# Accelerometer_Test_Board.net
KiCad netlist of a schematic drawn in EAGLE
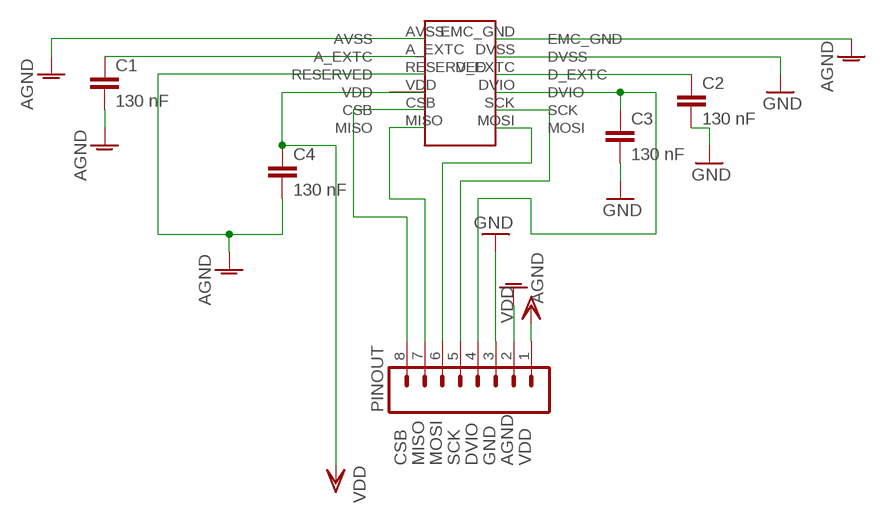
[diagram p0: schematic, sheet 1]

(export (version "E")
  (design (tool "Eeschema 10.0.6"))
  (components
    (comp (ref "C1")
      (value "130 nF")
      (footprint "eagle-import:0805")
      (libsource (lib "eagle-import") (part "CAP0805"))
    )
    (comp (ref "C2")
      (value "130 nF")
      (footprint "eagle-import:0805")
      (libsource (lib "eagle-import") (part "CAP0805"))
    )
    (comp (ref "C3")
      (value "130 nF")
      (footprint "eagle-import:0805")
      (libsource (lib "eagle-import") (part "CAP0805"))
    )
    (comp (ref "C4")
      (value "130 nF")
      (footprint "eagle-import:0805")
      (libsource (lib "eagle-import") (part "CAP0805"))
    )
    (comp (ref "PINOUT")
      (value "M08")
      (footprint "eagle-import:1X08")
      (libsource (lib "eagle-import") (part "M08"))
    )
    (comp (ref "U$1")
      (value "SCA3100-D04")
      (footprint "eagle-import:SCA3100-D04")
      (libsource (lib "eagle-import") (part "SCA3100-D04"))
    )
  )
  (nets
    (net (code "1") (name "/CSB") (class "Default")
      (node (ref "PINOUT") (pin "8") (pinfunction "8_8") (pintype "passive"))
      (node (ref "U$1") (pin "CSB") (pinfunction "CSB_CSB") (pintype "bidirectional"))
    )
    (net (code "2") (name "/DVIO") (class "Default")
      (node (ref "C3") (pin "1") (pinfunction "1_1") (pintype "passive"))
      (node (ref "PINOUT") (pin "4") (pinfunction "4_4") (pintype "passive"))
      (node (ref "U$1") (pin "DVIO") (pinfunction "DVIO_DVIO") (pintype "bidirectional"))
    )
    (net (code "3") (name "/MISO") (class "Default")
      (node (ref "PINOUT") (pin "7") (pinfunction "7_7") (pintype "passive"))
      (node (ref "U$1") (pin "MISO") (pinfunction "MISO_MISO") (pintype "bidirectional"))
    )
    (net (code "4") (name "/MOSI") (class "Default")
      (node (ref "PINOUT") (pin "6") (pinfunction "6_6") (pintype "passive"))
      (node (ref "U$1") (pin "MOSI") (pinfunction "MOSI_MOSI") (pintype "bidirectional"))
    )
    (net (code "5") (name "/SCK") (class "Default")
      (node (ref "PINOUT") (pin "5") (pinfunction "5_5") (pintype "passive"))
      (node (ref "U$1") (pin "SCK") (pinfunction "SCK_SCK") (pintype "bidirectional"))
    )
    (net (code "6") (name "AGND") (class "Default")
      (node (ref "C1") (pin "2") (pinfunction "2_2") (pintype "passive"))
      (node (ref "C4") (pin "2") (pinfunction "2_2") (pintype "passive"))
      (node (ref "PINOUT") (pin "2") (pinfunction "2_2") (pintype "passive"))
      (node (ref "U$1") (pin "AVSS") (pinfunction "AVSS_AVSS") (pintype "bidirectional"))
      (node (ref "U$1") (pin "EMC_GND") (pinfunction "EMC_GND_EMC_GND") (pintype "bidirectional"))
      (node (ref "U$1") (pin "RESERVED") (pinfunction "RESERVED_RESERVED") (pintype "bidirectional"))
    )
    (net (code "7") (name "GND") (class "Default")
      (node (ref "C2") (pin "2") (pinfunction "2_2") (pintype "passive"))
      (node (ref "C3") (pin "2") (pinfunction "2_2") (pintype "passive"))
      (node (ref "PINOUT") (pin "3") (pinfunction "3_3") (pintype "passive"))
      (node (ref "U$1") (pin "DVSS") (pinfunction "DVSS_DVSS") (pintype "bidirectional"))
    )
    (net (code "8") (name "Net-(C1-Pad1)") (class "Default")
      (node (ref "C1") (pin "1") (pinfunction "1_1") (pintype "passive"))
      (node (ref "U$1") (pin "A_EXTC") (pinfunction "A_EXTC_A_EXTC") (pintype "bidirectional"))
    )
    (net (code "9") (name "Net-(C2-Pad1)") (class "Default")
      (node (ref "C2") (pin "1") (pinfunction "1_1") (pintype "passive"))
      (node (ref "U$1") (pin "D_EXTC") (pinfunction "D_EXTC_D_EXTC") (pintype "bidirectional"))
    )
    (net (code "10") (name "VDD") (class "Default")
      (node (ref "C4") (pin "1") (pinfunction "1_1") (pintype "passive"))
      (node (ref "PINOUT") (pin "1") (pinfunction "1_1") (pintype "passive"))
      (node (ref "U$1") (pin "VDD") (pinfunction "VDD_VDD") (pintype "bidirectional"))
    )
  )
)
